# SD_Card.net
KiCad netlist of a schematic drawn in Altium Designer
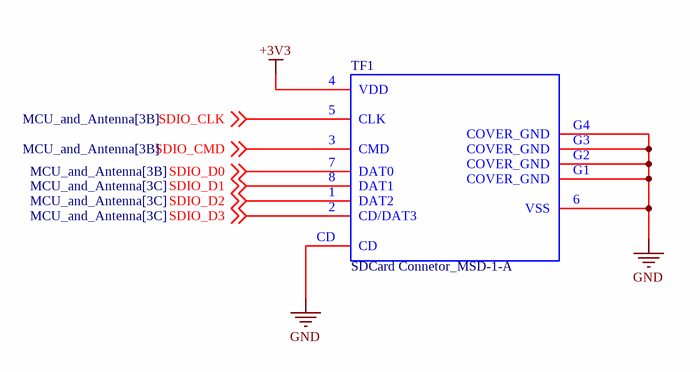
[diagram p0: SD_Card.SchDoc]

(export (version "E")
  (design (tool "Eeschema 10.0.6"))
  (components
    (comp (ref "TF1")
      (value "SDCard Connetor_MSD-1-A")
      (footprint "CUI_MSD-1-A")
      (description "Card Connector, Micro Sd, Push In Auto Eject Out Rohs Compliant: Yes ¦Same Sky MSD-1-A")
      (fields (field (name "MANUFACTURER") "Same Sky") (field (name "MANUFACTURER PART NUMBER") "MSD-1-A"))
      (libsource (lib "Schlib") (part "MSD-1-A"))
    )
  )
  (nets
    (net (code "1") (name "+3V3") (class "Default")
      (node (ref "TF1") (pin "4") (pinfunction "VDD_4") (pintype "passive"))
    )
    (net (code "2") (name "GND") (class "Default")
      (node (ref "TF1") (pin "6") (pinfunction "VSS_6") (pintype "passive"))
      (node (ref "TF1") (pin "CD") (pinfunction "CD_CD") (pintype "passive"))
      (node (ref "TF1") (pin "G1") (pinfunction "COVER_GND_G1") (pintype "passive"))
      (node (ref "TF1") (pin "G2") (pinfunction "COVER_GND_G2") (pintype "passive"))
      (node (ref "TF1") (pin "G3") (pinfunction "COVER_GND_G3") (pintype "passive"))
      (node (ref "TF1") (pin "G4") (pinfunction "COVER_GND_G4") (pintype "passive"))
    )
    (net (code "3") (name "SDIO_CLK") (class "Default")
      (node (ref "TF1") (pin "5") (pinfunction "CLK_5") (pintype "passive"))
    )
    (net (code "4") (name "SDIO_CMD") (class "Default")
      (node (ref "TF1") (pin "3") (pinfunction "CMD_3") (pintype "passive"))
    )
    (net (code "5") (name "SDIO_D0") (class "Default")
      (node (ref "TF1") (pin "7") (pinfunction "DAT0_7") (pintype "passive"))
    )
    (net (code "6") (name "SDIO_D1") (class "Default")
      (node (ref "TF1") (pin "8") (pinfunction "DAT1_8") (pintype "passive"))
    )
    (net (code "7") (name "SDIO_D2") (class "Default")
      (node (ref "TF1") (pin "1") (pinfunction "DAT2_1") (pintype "passive"))
    )
    (net (code "8") (name "SDIO_D3") (class "Default")
      (node (ref "TF1") (pin "2") (pinfunction "CD/DAT3_2") (pintype "passive"))
    )
  )
)
